# extension_board_header_xbee.net
KiCad netlist of a schematic drawn in EAGLE
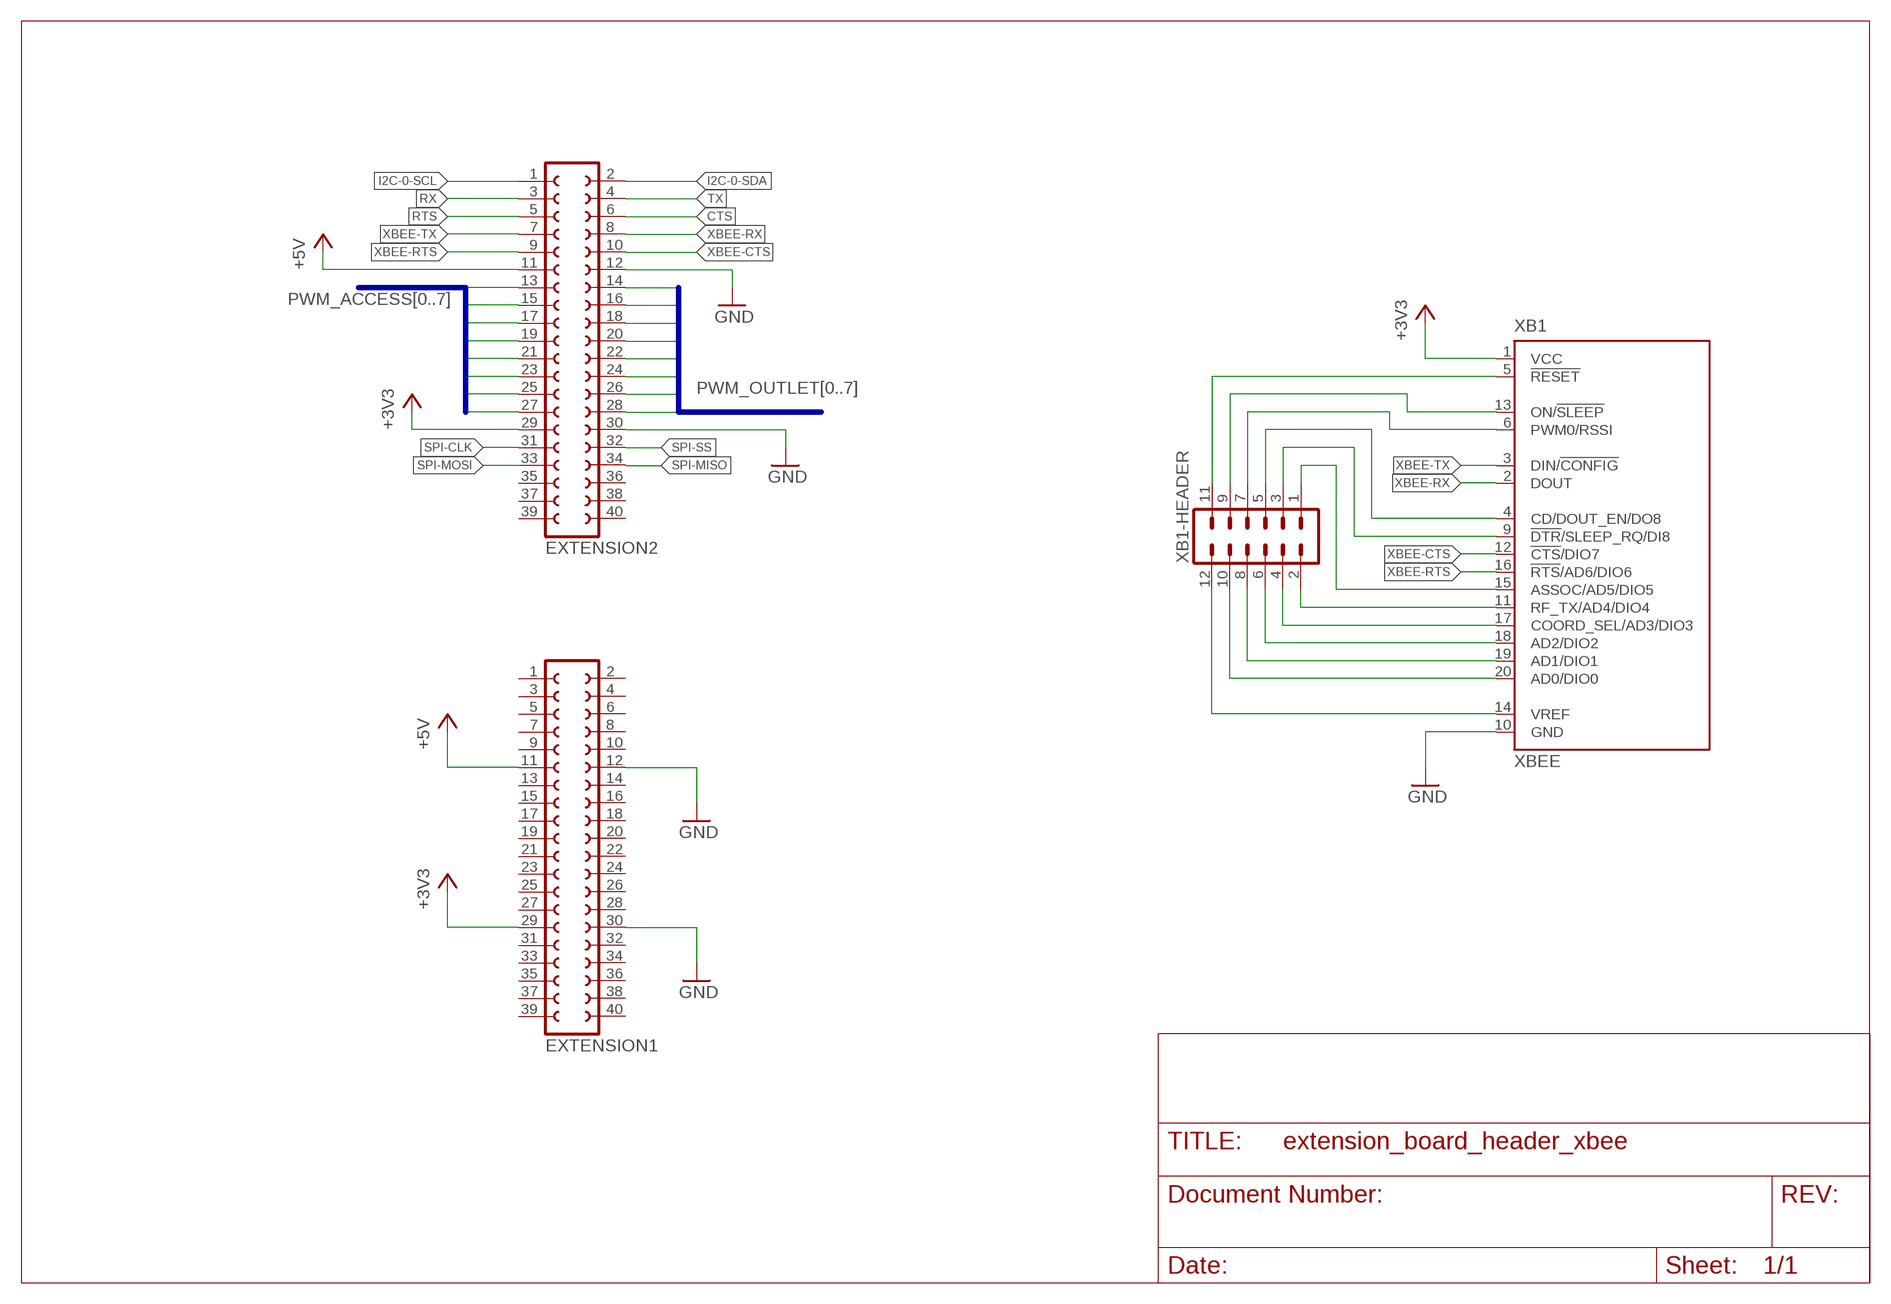
[diagram p0: schematic, sheet 1]

(export (version "E")
  (design (tool "Eeschema 10.0.6"))
  (components
    (comp (ref "EXTENSION1")
      (value "FE20-2")
      (footprint "eagle-import:FE20-2")
      (libsource (lib "eagle-import") (part "FE20-2"))
    )
    (comp (ref "EXTENSION2")
      (value "FE20-2")
      (footprint "eagle-import:FE20-2")
      (libsource (lib "eagle-import") (part "FE20-2"))
    )
    (comp (ref "XB1")
      (value "XBEE")
      (footprint "eagle-import:XBEE")
      (fields (field (name "MPN") "XBP24-Z7UIT-004"))
      (libsource (lib "eagle-import") (part "XBEE"))
    )
    (comp (ref "XB1-HEADER")
      (value "MA06-2")
      (footprint "eagle-import:MA06-2")
      (libsource (lib "eagle-import") (part "MA06-2"))
    )
  )
  (nets
    (net (code "17") (name "+3V3") (class "Default")
      (node (ref "EXTENSION1") (pin "29") (pinfunction "29_29") (pintype "passive"))
      (node (ref "EXTENSION2") (pin "29") (pinfunction "29_29") (pintype "passive"))
      (node (ref "XB1") (pin "1") (pinfunction "VCC_1") (pintype "power_in"))
    )
    (net (code "18") (name "+5V") (class "Default")
      (node (ref "EXTENSION1") (pin "11") (pinfunction "11_11") (pintype "passive"))
      (node (ref "EXTENSION2") (pin "11") (pinfunction "11_11") (pintype "passive"))
    )
    (net (code "21") (name "CTS") (class "Default")
      (node (ref "EXTENSION2") (pin "6") (pinfunction "6_6") (pintype "passive"))
    )
    (net (code "22") (name "GND") (class "Default")
      (node (ref "EXTENSION1") (pin "12") (pinfunction "12_12") (pintype "passive"))
      (node (ref "EXTENSION1") (pin "30") (pinfunction "30_30") (pintype "passive"))
      (node (ref "EXTENSION2") (pin "12") (pinfunction "12_12") (pintype "passive"))
      (node (ref "EXTENSION2") (pin "30") (pinfunction "30_30") (pintype "passive"))
      (node (ref "XB1") (pin "10") (pinfunction "GND_10") (pintype "power_in"))
    )
    (net (code "23") (name "I2C-0-SCL") (class "Default")
      (node (ref "EXTENSION2") (pin "1") (pinfunction "1_1") (pintype "passive"))
    )
    (net (code "24") (name "I2C-0-SDA") (class "Default")
      (node (ref "EXTENSION2") (pin "2") (pinfunction "2_2") (pintype "passive"))
    )
    (net (code "25") (name "Net-(XB1-AD0{slash}DIO0)") (class "Default")
      (node (ref "XB1") (pin "20") (pinfunction "AD0/DIO0_20") (pintype "bidirectional"))
      (node (ref "XB1-HEADER") (pin "10") (pinfunction "10_10") (pintype "passive"))
    )
    (net (code "26") (name "Net-(XB1-AD1{slash}DIO1)") (class "Default")
      (node (ref "XB1") (pin "19") (pinfunction "AD1/DIO1_19") (pintype "bidirectional"))
      (node (ref "XB1-HEADER") (pin "8") (pinfunction "8_8") (pintype "passive"))
    )
    (net (code "27") (name "Net-(XB1-AD2{slash}DIO2)") (class "Default")
      (node (ref "XB1") (pin "18") (pinfunction "AD2/DIO2_18") (pintype "bidirectional"))
      (node (ref "XB1-HEADER") (pin "6") (pinfunction "6_6") (pintype "passive"))
    )
    (net (code "28") (name "Net-(XB1-ASSOC{slash}AD5{slash}DIO5)") (class "Default")
      (node (ref "XB1") (pin "15") (pinfunction "ASSOC/AD5/DIO5_15") (pintype "bidirectional"))
      (node (ref "XB1-HEADER") (pin "1") (pinfunction "1_1") (pintype "passive"))
    )
    (net (code "29") (name "Net-(XB1-CD{slash}DOUT_EN{slash}DO8)") (class "Default")
      (node (ref "XB1") (pin "4") (pinfunction "CD/DOUT_EN/DO8_4") (pintype "output"))
      (node (ref "XB1-HEADER") (pin "5") (pinfunction "5_5") (pintype "passive"))
    )
    (net (code "30") (name "Net-(XB1-COORD_SEL{slash}AD3{slash}DIO3)") (class "Default")
      (node (ref "XB1") (pin "17") (pinfunction "COORD_SEL/AD3/DIO3_17") (pintype "bidirectional"))
      (node (ref "XB1-HEADER") (pin "4") (pinfunction "4_4") (pintype "passive"))
    )
    (net (code "31") (name "Net-(XB1-ON{slash}~{SLEEP})") (class "Default")
      (node (ref "XB1") (pin "13") (pinfunction "ON/~{SLEEP}_13") (pintype "output"))
      (node (ref "XB1-HEADER") (pin "9") (pinfunction "9_9") (pintype "passive"))
    )
    (net (code "32") (name "Net-(XB1-PWM0{slash}RSSI)") (class "Default")
      (node (ref "XB1") (pin "6") (pinfunction "PWM0/RSSI_6") (pintype "output"))
      (node (ref "XB1-HEADER") (pin "7") (pinfunction "7_7") (pintype "passive"))
    )
    (net (code "33") (name "Net-(XB1-RF_TX{slash}AD4{slash}DIO4)") (class "Default")
      (node (ref "XB1") (pin "11") (pinfunction "RF_TX/AD4/DIO4_11") (pintype "bidirectional"))
      (node (ref "XB1-HEADER") (pin "2") (pinfunction "2_2") (pintype "passive"))
    )
    (net (code "34") (name "Net-(XB1-VREF)") (class "Default")
      (node (ref "XB1") (pin "14") (pinfunction "VREF_14") (pintype "input"))
      (node (ref "XB1-HEADER") (pin "12") (pinfunction "12_12") (pintype "passive"))
    )
    (net (code "35") (name "Net-(XB1-~{DTR}{slash}SLEEP_RQ{slash}DI8)") (class "Default")
      (node (ref "XB1") (pin "9") (pinfunction "~{DTR}/SLEEP_RQ/DI8_9") (pintype "bidirectional"))
      (node (ref "XB1-HEADER") (pin "3") (pinfunction "3_3") (pintype "passive"))
    )
    (net (code "36") (name "Net-(XB1-~{RESET})") (class "Default")
      (node (ref "XB1") (pin "5") (pinfunction "~{RESET}_5") (pintype "input"))
      (node (ref "XB1-HEADER") (pin "11") (pinfunction "11_11") (pintype "passive"))
    )
    (net (code "37") (name "RTS") (class "Default")
      (node (ref "EXTENSION2") (pin "5") (pinfunction "5_5") (pintype "passive"))
    )
    (net (code "38") (name "RX") (class "Default")
      (node (ref "EXTENSION2") (pin "3") (pinfunction "3_3") (pintype "passive"))
    )
    (net (code "39") (name "SPI-CLK") (class "Default")
      (node (ref "EXTENSION2") (pin "31") (pinfunction "31_31") (pintype "passive"))
    )
    (net (code "40") (name "SPI-MISO") (class "Default")
      (node (ref "EXTENSION2") (pin "34") (pinfunction "34_34") (pintype "passive"))
    )
    (net (code "41") (name "SPI-MOSI") (class "Default")
      (node (ref "EXTENSION2") (pin "33") (pinfunction "33_33") (pintype "passive"))
    )
    (net (code "42") (name "SPI-SS") (class "Default")
      (node (ref "EXTENSION2") (pin "32") (pinfunction "32_32") (pintype "passive"))
    )
    (net (code "43") (name "TX") (class "Default")
      (node (ref "EXTENSION2") (pin "4") (pinfunction "4_4") (pintype "passive"))
    )
    (net (code "44") (name "XBEE-CTS") (class "Default")
      (node (ref "EXTENSION2") (pin "10") (pinfunction "10_10") (pintype "passive"))
      (node (ref "XB1") (pin "12") (pinfunction "~{CTS}/DIO7_12") (pintype "bidirectional"))
    )
    (net (code "45") (name "XBEE-RTS") (class "Default")
      (node (ref "EXTENSION2") (pin "9") (pinfunction "9_9") (pintype "passive"))
      (node (ref "XB1") (pin "16") (pinfunction "~{RTS}/AD6/DIO6_16") (pintype "bidirectional"))
    )
    (net (code "46") (name "XBEE-RX") (class "Default")
      (node (ref "EXTENSION2") (pin "8") (pinfunction "8_8") (pintype "passive"))
      (node (ref "XB1") (pin "2") (pinfunction "DOUT_2") (pintype "output"))
    )
    (net (code "47") (name "XBEE-TX") (class "Default")
      (node (ref "EXTENSION2") (pin "7") (pinfunction "7_7") (pintype "passive"))
      (node (ref "XB1") (pin "3") (pinfunction "DIN/~{CONFIG}_3") (pintype "input"))
    )
    (net (code "48") (name "unconnected-(EXTENSION1-Pad1)") (class "Default")
      (node (ref "EXTENSION1") (pin "1") (pinfunction "1_1") (pintype "passive"))
    )
    (net (code "49") (name "unconnected-(EXTENSION1-Pad2)") (class "Default")
      (node (ref "EXTENSION1") (pin "2") (pinfunction "2_2") (pintype "passive"))
    )
    (net (code "50") (name "unconnected-(EXTENSION1-Pad3)") (class "Default")
      (node (ref "EXTENSION1") (pin "3") (pinfunction "3_3") (pintype "passive"))
    )
    (net (code "51") (name "unconnected-(EXTENSION1-Pad4)") (class "Default")
      (node (ref "EXTENSION1") (pin "4") (pinfunction "4_4") (pintype "passive"))
    )
    (net (code "52") (name "unconnected-(EXTENSION1-Pad5)") (class "Default")
      (node (ref "EXTENSION1") (pin "5") (pinfunction "5_5") (pintype "passive"))
    )
    (net (code "53") (name "unconnected-(EXTENSION1-Pad6)") (class "Default")
      (node (ref "EXTENSION1") (pin "6") (pinfunction "6_6") (pintype "passive"))
    )
    (net (code "54") (name "unconnected-(EXTENSION1-Pad7)") (class "Default")
      (node (ref "EXTENSION1") (pin "7") (pinfunction "7_7") (pintype "passive"))
    )
    (net (code "55") (name "unconnected-(EXTENSION1-Pad8)") (class "Default")
      (node (ref "EXTENSION1") (pin "8") (pinfunction "8_8") (pintype "passive"))
    )
    (net (code "56") (name "unconnected-(EXTENSION1-Pad9)") (class "Default")
      (node (ref "EXTENSION1") (pin "9") (pinfunction "9_9") (pintype "passive"))
    )
    (net (code "57") (name "unconnected-(EXTENSION1-Pad10)") (class "Default")
      (node (ref "EXTENSION1") (pin "10") (pinfunction "10_10") (pintype "passive"))
    )
    (net (code "58") (name "unconnected-(EXTENSION1-Pad13)") (class "Default")
      (node (ref "EXTENSION1") (pin "13") (pinfunction "13_13") (pintype "passive"))
    )
    (net (code "59") (name "unconnected-(EXTENSION1-Pad14)") (class "Default")
      (node (ref "EXTENSION1") (pin "14") (pinfunction "14_14") (pintype "passive"))
    )
    (net (code "60") (name "unconnected-(EXTENSION1-Pad15)") (class "Default")
      (node (ref "EXTENSION1") (pin "15") (pinfunction "15_15") (pintype "passive"))
    )
    (net (code "61") (name "unconnected-(EXTENSION1-Pad16)") (class "Default")
      (node (ref "EXTENSION1") (pin "16") (pinfunction "16_16") (pintype "passive"))
    )
    (net (code "62") (name "unconnected-(EXTENSION1-Pad17)") (class "Default")
      (node (ref "EXTENSION1") (pin "17") (pinfunction "17_17") (pintype "passive"))
    )
    (net (code "63") (name "unconnected-(EXTENSION1-Pad18)") (class "Default")
      (node (ref "EXTENSION1") (pin "18") (pinfunction "18_18") (pintype "passive"))
    )
    (net (code "64") (name "unconnected-(EXTENSION1-Pad19)") (class "Default")
      (node (ref "EXTENSION1") (pin "19") (pinfunction "19_19") (pintype "passive"))
    )
    (net (code "65") (name "unconnected-(EXTENSION1-Pad20)") (class "Default")
      (node (ref "EXTENSION1") (pin "20") (pinfunction "20_20") (pintype "passive"))
    )
    (net (code "66") (name "unconnected-(EXTENSION1-Pad21)") (class "Default")
      (node (ref "EXTENSION1") (pin "21") (pinfunction "21_21") (pintype "passive"))
    )
    (net (code "67") (name "unconnected-(EXTENSION1-Pad22)") (class "Default")
      (node (ref "EXTENSION1") (pin "22") (pinfunction "22_22") (pintype "passive"))
    )
    (net (code "68") (name "unconnected-(EXTENSION1-Pad23)") (class "Default")
      (node (ref "EXTENSION1") (pin "23") (pinfunction "23_23") (pintype "passive"))
    )
    (net (code "69") (name "unconnected-(EXTENSION1-Pad24)") (class "Default")
      (node (ref "EXTENSION1") (pin "24") (pinfunction "24_24") (pintype "passive"))
    )
    (net (code "70") (name "unconnected-(EXTENSION1-Pad25)") (class "Default")
      (node (ref "EXTENSION1") (pin "25") (pinfunction "25_25") (pintype "passive"))
    )
    (net (code "71") (name "unconnected-(EXTENSION1-Pad26)") (class "Default")
      (node (ref "EXTENSION1") (pin "26") (pinfunction "26_26") (pintype "passive"))
    )
    (net (code "72") (name "unconnected-(EXTENSION1-Pad27)") (class "Default")
      (node (ref "EXTENSION1") (pin "27") (pinfunction "27_27") (pintype "passive"))
    )
    (net (code "73") (name "unconnected-(EXTENSION1-Pad28)") (class "Default")
      (node (ref "EXTENSION1") (pin "28") (pinfunction "28_28") (pintype "passive"))
    )
    (net (code "74") (name "unconnected-(EXTENSION1-Pad31)") (class "Default")
      (node (ref "EXTENSION1") (pin "31") (pinfunction "31_31") (pintype "passive"))
    )
    (net (code "75") (name "unconnected-(EXTENSION1-Pad32)") (class "Default")
      (node (ref "EXTENSION1") (pin "32") (pinfunction "32_32") (pintype "passive"))
    )
    (net (code "76") (name "unconnected-(EXTENSION1-Pad33)") (class "Default")
      (node (ref "EXTENSION1") (pin "33") (pinfunction "33_33") (pintype "passive"))
    )
    (net (code "77") (name "unconnected-(EXTENSION1-Pad34)") (class "Default")
      (node (ref "EXTENSION1") (pin "34") (pinfunction "34_34") (pintype "passive"))
    )
    (net (code "78") (name "unconnected-(EXTENSION1-Pad35)") (class "Default")
      (node (ref "EXTENSION1") (pin "35") (pinfunction "35_35") (pintype "passive"))
    )
    (net (code "79") (name "unconnected-(EXTENSION1-Pad36)") (class "Default")
      (node (ref "EXTENSION1") (pin "36") (pinfunction "36_36") (pintype "passive"))
    )
    (net (code "80") (name "unconnected-(EXTENSION1-Pad37)") (class "Default")
      (node (ref "EXTENSION1") (pin "37") (pinfunction "37_37") (pintype "passive"))
    )
    (net (code "81") (name "unconnected-(EXTENSION1-Pad38)") (class "Default")
      (node (ref "EXTENSION1") (pin "38") (pinfunction "38_38") (pintype "passive"))
    )
    (net (code "82") (name "unconnected-(EXTENSION1-Pad39)") (class "Default")
      (node (ref "EXTENSION1") (pin "39") (pinfunction "39_39") (pintype "passive"))
    )
    (net (code "83") (name "unconnected-(EXTENSION1-Pad40)") (class "Default")
      (node (ref "EXTENSION1") (pin "40") (pinfunction "40_40") (pintype "passive"))
    )
    (net (code "84") (name "unconnected-(EXTENSION2-Pad13)") (class "Default")
      (node (ref "EXTENSION2") (pin "13") (pinfunction "13_13") (pintype "passive"))
    )
    (net (code "85") (name "unconnected-(EXTENSION2-Pad14)") (class "Default")
      (node (ref "EXTENSION2") (pin "14") (pinfunction "14_14") (pintype "passive"))
    )
    (net (code "86") (name "unconnected-(EXTENSION2-Pad15)") (class "Default")
      (node (ref "EXTENSION2") (pin "15") (pinfunction "15_15") (pintype "passive"))
    )
    (net (code "87") (name "unconnected-(EXTENSION2-Pad16)") (class "Default")
      (node (ref "EXTENSION2") (pin "16") (pinfunction "16_16") (pintype "passive"))
    )
    (net (code "88") (name "unconnected-(EXTENSION2-Pad17)") (class "Default")
      (node (ref "EXTENSION2") (pin "17") (pinfunction "17_17") (pintype "passive"))
    )
    (net (code "89") (name "unconnected-(EXTENSION2-Pad18)") (class "Default")
      (node (ref "EXTENSION2") (pin "18") (pinfunction "18_18") (pintype "passive"))
    )
    (net (code "90") (name "unconnected-(EXTENSION2-Pad19)") (class "Default")
      (node (ref "EXTENSION2") (pin "19") (pinfunction "19_19") (pintype "passive"))
    )
    (net (code "91") (name "unconnected-(EXTENSION2-Pad20)") (class "Default")
      (node (ref "EXTENSION2") (pin "20") (pinfunction "20_20") (pintype "passive"))
    )
    (net (code "92") (name "unconnected-(EXTENSION2-Pad21)") (class "Default")
      (node (ref "EXTENSION2") (pin "21") (pinfunction "21_21") (pintype "passive"))
    )
    (net (code "93") (name "unconnected-(EXTENSION2-Pad22)") (class "Default")
      (node (ref "EXTENSION2") (pin "22") (pinfunction "22_22") (pintype "passive"))
    )
    (net (code "94") (name "unconnected-(EXTENSION2-Pad23)") (class "Default")
      (node (ref "EXTENSION2") (pin "23") (pinfunction "23_23") (pintype "passive"))
    )
    (net (code "95") (name "unconnected-(EXTENSION2-Pad24)") (class "Default")
      (node (ref "EXTENSION2") (pin "24") (pinfunction "24_24") (pintype "passive"))
    )
    (net (code "96") (name "unconnected-(EXTENSION2-Pad25)") (class "Default")
      (node (ref "EXTENSION2") (pin "25") (pinfunction "25_25") (pintype "passive"))
    )
    (net (code "97") (name "unconnected-(EXTENSION2-Pad26)") (class "Default")
      (node (ref "EXTENSION2") (pin "26") (pinfunction "26_26") (pintype "passive"))
    )
    (net (code "98") (name "unconnected-(EXTENSION2-Pad27)") (class "Default")
      (node (ref "EXTENSION2") (pin "27") (pinfunction "27_27") (pintype "passive"))
    )
    (net (code "99") (name "unconnected-(EXTENSION2-Pad28)") (class "Default")
      (node (ref "EXTENSION2") (pin "28") (pinfunction "28_28") (pintype "passive"))
    )
    (net (code "100") (name "unconnected-(EXTENSION2-Pad35)") (class "Default")
      (node (ref "EXTENSION2") (pin "35") (pinfunction "35_35") (pintype "passive"))
    )
    (net (code "101") (name "unconnected-(EXTENSION2-Pad36)") (class "Default")
      (node (ref "EXTENSION2") (pin "36") (pinfunction "36_36") (pintype "passive"))
    )
    (net (code "102") (name "unconnected-(EXTENSION2-Pad37)") (class "Default")
      (node (ref "EXTENSION2") (pin "37") (pinfunction "37_37") (pintype "passive"))
    )
    (net (code "103") (name "unconnected-(EXTENSION2-Pad38)") (class "Default")
      (node (ref "EXTENSION2") (pin "38") (pinfunction "38_38") (pintype "passive"))
    )
    (net (code "104") (name "unconnected-(EXTENSION2-Pad39)") (class "Default")
      (node (ref "EXTENSION2") (pin "39") (pinfunction "39_39") (pintype "passive"))
    )
    (net (code "105") (name "unconnected-(EXTENSION2-Pad40)") (class "Default")
      (node (ref "EXTENSION2") (pin "40") (pinfunction "40_40") (pintype "passive"))
    )
  )
)
